# USBConverter.net
KiCad netlist of a schematic drawn in Altium Designer
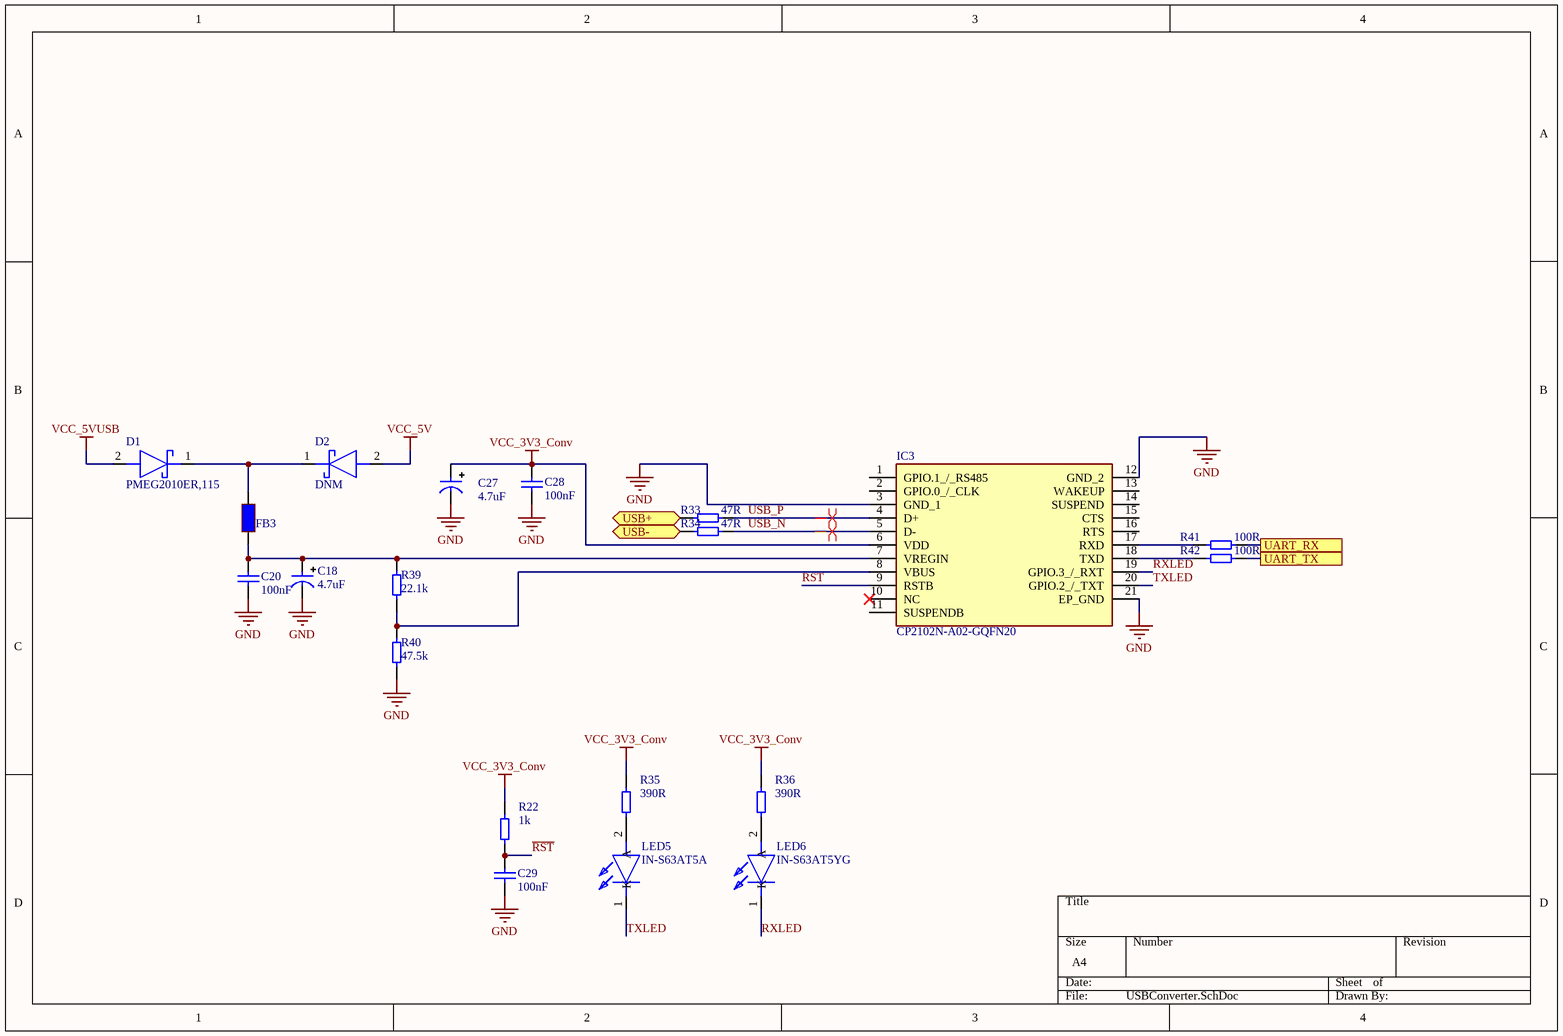
[diagram p0: USBConverter.SchDoc]

(export (version "E")
  (design (tool "Eeschema 10.0.6"))
  (components
    (comp (ref "C18")
      (value "4.7uF")
      (footprint "A_3216")
      (description "Polarized Tantalum Capacitor")
      (fields (field (name "PART NUMBER") "C_Case_A_3216") (field (name "MANUFACTURER") "AVX"))
      (libsource (lib "ZUIAM_LIB") (part "CAP_POL"))
    )
    (comp (ref "C20")
      (value "100nF")
      (footprint "0603-Capacitor")
      (description "Capacitor")
      (fields (field (name "PART NUMBER") "C0603"))
      (libsource (lib "ZUIAM_LIB") (part "Capacitor"))
    )
    (comp (ref "C27")
      (value "4.7uF")
      (footprint "A_3216")
      (description "Polarized Tantalum Capacitor")
      (fields (field (name "PART NUMBER") "C_Case_A_3216") (field (name "MANUFACTURER") "AVX"))
      (libsource (lib "ZUIAM_LIB") (part "CAP_POL"))
    )
    (comp (ref "C28")
      (value "100nF")
      (footprint "0603-Capacitor")
      (description "Capacitor")
      (fields (field (name "PART NUMBER") "C0603"))
      (libsource (lib "ZUIAM_LIB") (part "Capacitor"))
    )
    (comp (ref "C29")
      (value "100nF")
      (footprint "0603-Capacitor")
      (description "Capacitor")
      (fields (field (name "PART NUMBER") "C0603"))
      (libsource (lib "ZUIAM_LIB") (part "Capacitor"))
    )
    (comp (ref "D1")
      (value "PMEG2010ER,115")
      (footprint "MouserDropbox:SODFL3517X110N")
      (description "Schottky Diode")
      (fields
        (field (name "MOUSER PART NUMBER") "771-PMEG2010ER115")
        (field (name "RS PART NUMBER") "8166824P")
      )
      (libsource (lib "*") (part "PMEG2010ER,115"))
    )
    (comp (ref "D2")
      (value "DNM")
      (footprint "MouserDropbox:SODFL3517X110N")
      (description "Schottky Diode")
      (fields
        (field (name "MANUFACTURER_PART_NUMBER") "PMEG2010ER,115")
        (field (name "MOUSER PART NUMBER") "771-PMEG2010ER115")
      )
      (libsource (lib "*") (part "PMEG2010ER,115"))
    )
    (comp (ref "FB3")
      (value "BLM18HE152SN1D")
      (footprint "0603-Ferrite bead")
      (description "Ferrite Bead")
      (fields (field (name "MANUFACTURER") "Murata"))
      (libsource (lib "ZUIAM_LIB") (part "Ferrite_bead"))
    )
    (comp (ref "IC3")
      (value "CP2102N-A02-GQFN20")
      (footprint "MouserDropbox:CP2102NA02GQFN20")
      (description "Integrated Circuit")
      (fields
        (field (name "MOUSER PART NUMBER") "634-CP2102NA02GQFN20")
        (field (name "RS PART NUMBER") "1871330")
      )
      (libsource (lib "*") (part "CP2102N-A02-GQFN20"))
    )
    (comp (ref "LED5")
      (value "IN-S63AT5A")
      (footprint "LEDM168X39N")
      (description "LED")
      (fields (field (name "MOUSER PART NUMBER") "743-IN-S63AT5G"))
      (libsource (lib "mouser") (part "IN-S63AT5G"))
    )
    (comp (ref "LED6")
      (value "IN-S63AT5YG")
      (footprint "LEDM168X39N")
      (description "LED")
      (fields (field (name "MOUSER PART NUMBER") "743-IN-S63AT5G"))
      (libsource (lib "mouser") (part "IN-S63AT5G"))
    )
    (comp (ref "R22")
      (value "1k")
      (footprint "0603-Resistor")
      (description "Resistor")
      (fields (field (name "PART NUMBER") "R0603"))
      (libsource (lib "") (part "Resistor_2"))
    )
    (comp (ref "R33")
      (value "47R")
      (footprint "0603-Resistor")
      (description "Resistor")
      (fields (field (name "PART NUMBER") "R0603"))
      (libsource (lib "ZUIAM_LIB") (part "Resistor"))
    )
    (comp (ref "R34")
      (value "47R")
      (footprint "0603-Resistor")
      (description "Resistor")
      (fields (field (name "PART NUMBER") "R0603"))
      (libsource (lib "ZUIAM_LIB") (part "Resistor"))
    )
    (comp (ref "R35")
      (value "390R")
      (footprint "0603-Resistor")
      (description "Resistor")
      (fields (field (name "PART NUMBER") "R0603"))
      (libsource (lib "") (part "Resistor_2"))
    )
    (comp (ref "R36")
      (value "390R")
      (footprint "0603-Resistor")
      (description "Resistor")
      (fields (field (name "PART NUMBER") "R0603"))
      (libsource (lib "") (part "Resistor_2"))
    )
    (comp (ref "R39")
      (value "22.1k")
      (footprint "0603-Resistor")
      (description "Resistor")
      (fields (field (name "PART NUMBER") "R0603"))
      (libsource (lib "") (part "Resistor_1"))
    )
    (comp (ref "R40")
      (value "47.5k")
      (footprint "0603-Resistor")
      (description "Resistor")
      (fields (field (name "PART NUMBER") "R0603"))
      (libsource (lib "") (part "Resistor_1"))
    )
    (comp (ref "R41")
      (value "100R")
      (footprint "0603-Resistor")
      (description "Resistor")
      (fields (field (name "PART NUMBER") "R0603"))
      (libsource (lib "ZUIAM_LIB") (part "Resistor"))
    )
    (comp (ref "R42")
      (value "100R")
      (footprint "0603-Resistor")
      (description "Resistor")
      (fields (field (name "PART NUMBER") "R0603"))
      (libsource (lib "ZUIAM_LIB") (part "Resistor"))
    )
  )
  (nets
    (net (code "1") (name "/RXLED") (class "Default")
      (node (ref "IC3") (pin "19") (pinfunction "GPIO.3_/_RXT_19") (pintype "passive"))
      (node (ref "LED6") (pin "1") (pinfunction "K_1") (pintype "passive"))
    )
    (net (code "2") (name "/TXLED") (class "Default")
      (node (ref "IC3") (pin "20") (pinfunction "GPIO.2_/_TXT_20") (pintype "passive"))
      (node (ref "LED5") (pin "1") (pinfunction "K_1") (pintype "passive"))
    )
    (net (code "3") (name "/UART_RX") (class "Default")
      (node (ref "R41") (pin "1") (pinfunction "1_1") (pintype "passive"))
    )
    (net (code "4") (name "/UART_TX") (class "Default")
      (node (ref "R42") (pin "1") (pinfunction "1_1") (pintype "passive"))
    )
    (net (code "5") (name "/USB+") (class "Default")
      (node (ref "R33") (pin "2") (pinfunction "2_2") (pintype "passive"))
    )
    (net (code "6") (name "/USB-") (class "Default")
      (node (ref "R34") (pin "2") (pinfunction "2_2") (pintype "passive"))
    )
    (net (code "7") (name "/USB_N") (class "Default")
      (node (ref "IC3") (pin "5") (pinfunction "D-_5") (pintype "passive"))
      (node (ref "R34") (pin "1") (pinfunction "1_1") (pintype "passive"))
    )
    (net (code "8") (name "/USB_P") (class "Default")
      (node (ref "IC3") (pin "4") (pinfunction "D+_4") (pintype "passive"))
      (node (ref "R33") (pin "1") (pinfunction "1_1") (pintype "passive"))
    )
    (net (code "9") (name "/~{RST}") (class "Default")
      (node (ref "C29") (pin "1") (pinfunction "1_1") (pintype "passive"))
      (node (ref "IC3") (pin "9") (pinfunction "RSTB_9") (pintype "passive"))
      (node (ref "R22") (pin "1") (pinfunction "1_1") (pintype "passive"))
    )
    (net (code "10") (name "GND") (class "Default")
      (node (ref "C18") (pin "2") (pinfunction "2_2") (pintype "passive"))
      (node (ref "C20") (pin "2") (pinfunction "2_2") (pintype "passive"))
      (node (ref "C27") (pin "2") (pinfunction "2_2") (pintype "passive"))
      (node (ref "C28") (pin "2") (pinfunction "2_2") (pintype "passive"))
      (node (ref "C29") (pin "2") (pinfunction "2_2") (pintype "passive"))
      (node (ref "IC3") (pin "12") (pinfunction "GND_2_12") (pintype "passive"))
      (node (ref "IC3") (pin "21") (pinfunction "EP_GND_21") (pintype "passive"))
      (node (ref "IC3") (pin "3") (pinfunction "GND_1_3") (pintype "passive"))
      (node (ref "R40") (pin "2") (pinfunction "2_2") (pintype "passive"))
    )
    (net (code "11") (name "Net-(D1-K)") (class "Default")
      (node (ref "D1") (pin "1") (pinfunction "K_1") (pintype "passive"))
      (node (ref "D2") (pin "1") (pinfunction "K_1") (pintype "passive"))
      (node (ref "FB3") (pin "2") (pinfunction "2_2") (pintype "passive"))
    )
    (net (code "12") (name "Net-(IC3-RXD)") (class "Default")
      (node (ref "IC3") (pin "17") (pinfunction "RXD_17") (pintype "passive"))
      (node (ref "R41") (pin "2") (pinfunction "2_2") (pintype "passive"))
    )
    (net (code "13") (name "Net-(IC3-TXD)") (class "Default")
      (node (ref "IC3") (pin "18") (pinfunction "TXD_18") (pintype "passive"))
      (node (ref "R42") (pin "2") (pinfunction "2_2") (pintype "passive"))
    )
    (net (code "14") (name "Net-(IC3-VBUS)") (class "Default")
      (node (ref "IC3") (pin "8") (pinfunction "VBUS_8") (pintype "passive"))
      (node (ref "R39") (pin "2") (pinfunction "2_2") (pintype "passive"))
      (node (ref "R40") (pin "1") (pinfunction "1_1") (pintype "passive"))
    )
    (net (code "15") (name "Net-(IC3-VREGIN)") (class "Default")
      (node (ref "C18") (pin "1") (pinfunction "1_1") (pintype "passive"))
      (node (ref "C20") (pin "1") (pinfunction "1_1") (pintype "passive"))
      (node (ref "FB3") (pin "1") (pinfunction "1_1") (pintype "passive"))
      (node (ref "IC3") (pin "7") (pinfunction "VREGIN_7") (pintype "passive"))
      (node (ref "R39") (pin "1") (pinfunction "1_1") (pintype "passive"))
    )
    (net (code "16") (name "Net-(LED5-A)") (class "Default")
      (node (ref "LED5") (pin "2") (pinfunction "A_2") (pintype "passive"))
      (node (ref "R35") (pin "1") (pinfunction "1_1") (pintype "passive"))
    )
    (net (code "17") (name "Net-(LED6-A)") (class "Default")
      (node (ref "LED6") (pin "2") (pinfunction "A_2") (pintype "passive"))
      (node (ref "R36") (pin "1") (pinfunction "1_1") (pintype "passive"))
    )
    (net (code "18") (name "VCC_3V3_Conv") (class "Default")
      (node (ref "C27") (pin "1") (pinfunction "1_1") (pintype "passive"))
      (node (ref "C28") (pin "1") (pinfunction "1_1") (pintype "passive"))
      (node (ref "IC3") (pin "6") (pinfunction "VDD_6") (pintype "passive"))
      (node (ref "R22") (pin "2") (pinfunction "2_2") (pintype "passive"))
      (node (ref "R35") (pin "2") (pinfunction "2_2") (pintype "passive"))
      (node (ref "R36") (pin "2") (pinfunction "2_2") (pintype "passive"))
    )
    (net (code "19") (name "VCC_5V") (class "Default")
      (node (ref "D2") (pin "2") (pinfunction "A_2") (pintype "passive"))
    )
    (net (code "20") (name "VCC_5VUSB") (class "Default")
      (node (ref "D1") (pin "2") (pinfunction "A_2") (pintype "passive"))
    )
    (net (code "21") (name "unconnected-(IC3-CTS-Pad15)") (class "Default")
      (node (ref "IC3") (pin "15") (pinfunction "CTS_15") (pintype "passive"))
    )
    (net (code "22") (name "unconnected-(IC3-GPIO.0_{slash}_CLK-Pad2)") (class "Default")
      (node (ref "IC3") (pin "2") (pinfunction "GPIO.0_/_CLK_2") (pintype "passive"))
    )
    (net (code "23") (name "unconnected-(IC3-GPIO.1_{slash}_RS485-Pad1)") (class "Default")
      (node (ref "IC3") (pin "1") (pinfunction "GPIO.1_/_RS485_1") (pintype "passive"))
    )
    (net (code "24") (name "unconnected-(IC3-NC-Pad10)") (class "Default")
      (node (ref "IC3") (pin "10") (pinfunction "NC_10") (pintype "passive+no_connect"))
    )
    (net (code "25") (name "unconnected-(IC3-RTS-Pad16)") (class "Default")
      (node (ref "IC3") (pin "16") (pinfunction "RTS_16") (pintype "passive"))
    )
    (net (code "26") (name "unconnected-(IC3-SUSPEND-Pad14)") (class "Default")
      (node (ref "IC3") (pin "14") (pinfunction "SUSPEND_14") (pintype "passive"))
    )
    (net (code "27") (name "unconnected-(IC3-SUSPENDB-Pad11)") (class "Default")
      (node (ref "IC3") (pin "11") (pinfunction "SUSPENDB_11") (pintype "passive"))
    )
    (net (code "28") (name "unconnected-(IC3-WAKEUP-Pad13)") (class "Default")
      (node (ref "IC3") (pin "13") (pinfunction "WAKEUP_13") (pintype "passive"))
    )
  )
)
